# IO_wing.net
KiCad netlist of a schematic drawn in EAGLE
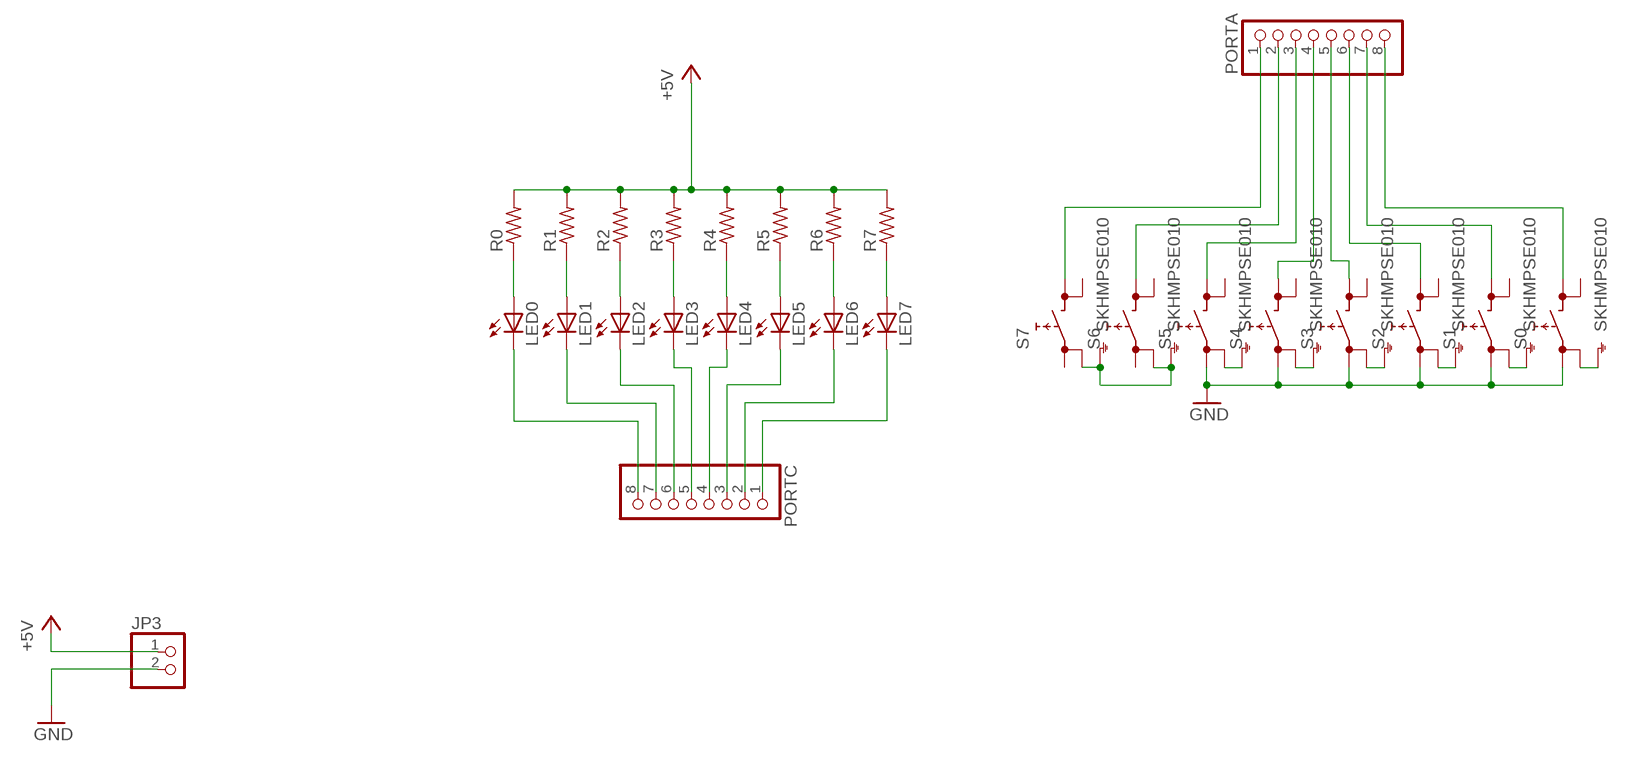
[diagram p0: schematic, sheet 1]

(export (version "E")
  (design (tool "Eeschema 10.0.6"))
  (components
    (comp (ref "JP3")
      (value "PINHD-1X2")
      (footprint "eagle-import:1X02")
      (libsource (lib "eagle-import") (part "PINHD-1X2"))
    )
    (comp (ref "LED0")
      (value "LEDCHIP-LED0805")
      (footprint "eagle-import:CHIP-LED0805")
      (libsource (lib "eagle-import") (part "LEDCHIP-LED0805"))
    )
    (comp (ref "LED1")
      (value "LEDCHIP-LED0805")
      (footprint "eagle-import:CHIP-LED0805")
      (libsource (lib "eagle-import") (part "LEDCHIP-LED0805"))
    )
    (comp (ref "LED2")
      (value "LEDCHIP-LED0805")
      (footprint "eagle-import:CHIP-LED0805")
      (libsource (lib "eagle-import") (part "LEDCHIP-LED0805"))
    )
    (comp (ref "LED3")
      (value "LEDCHIP-LED0805")
      (footprint "eagle-import:CHIP-LED0805")
      (libsource (lib "eagle-import") (part "LEDCHIP-LED0805"))
    )
    (comp (ref "LED4")
      (value "LEDCHIP-LED0805")
      (footprint "eagle-import:CHIP-LED0805")
      (libsource (lib "eagle-import") (part "LEDCHIP-LED0805"))
    )
    (comp (ref "LED5")
      (value "LEDCHIP-LED0805")
      (footprint "eagle-import:CHIP-LED0805")
      (libsource (lib "eagle-import") (part "LEDCHIP-LED0805"))
    )
    (comp (ref "LED6")
      (value "LEDCHIP-LED0805")
      (footprint "eagle-import:CHIP-LED0805")
      (libsource (lib "eagle-import") (part "LEDCHIP-LED0805"))
    )
    (comp (ref "LED7")
      (value "LEDCHIP-LED0805")
      (footprint "eagle-import:CHIP-LED0805")
      (libsource (lib "eagle-import") (part "LEDCHIP-LED0805"))
    )
    (comp (ref "PORTA")
      (value "PINHD-1X8")
      (footprint "eagle-import:1X08")
      (libsource (lib "eagle-import") (part "PINHD-1X8"))
    )
    (comp (ref "PORTC")
      (value "PINHD-1X8")
      (footprint "eagle-import:1X08")
      (libsource (lib "eagle-import") (part "PINHD-1X8"))
    )
    (comp (ref "R0")
      (value "R-US_R0805")
      (footprint "eagle-import:R0805")
      (libsource (lib "eagle-import") (part "R-US_R0805"))
    )
    (comp (ref "R1")
      (value "R-US_R0805")
      (footprint "eagle-import:R0805")
      (libsource (lib "eagle-import") (part "R-US_R0805"))
    )
    (comp (ref "R2")
      (value "R-US_R0805")
      (footprint "eagle-import:R0805")
      (libsource (lib "eagle-import") (part "R-US_R0805"))
    )
    (comp (ref "R3")
      (value "R-US_R0805")
      (footprint "eagle-import:R0805")
      (libsource (lib "eagle-import") (part "R-US_R0805"))
    )
    (comp (ref "R4")
      (value "R-US_R0805")
      (footprint "eagle-import:R0805")
      (libsource (lib "eagle-import") (part "R-US_R0805"))
    )
    (comp (ref "R5")
      (value "R-US_R0805")
      (footprint "eagle-import:R0805")
      (libsource (lib "eagle-import") (part "R-US_R0805"))
    )
    (comp (ref "R6")
      (value "R-US_R0805")
      (footprint "eagle-import:R0805")
      (libsource (lib "eagle-import") (part "R-US_R0805"))
    )
    (comp (ref "R7")
      (value "R-US_R0805")
      (footprint "eagle-import:R0805")
      (libsource (lib "eagle-import") (part "R-US_R0805"))
    )
    (comp (ref "S0")
      (value "SKHMPSE010")
      (footprint "eagle-import:SKHMPXE010")
      (libsource (lib "eagle-import") (part "SKHMPE010S"))
    )
    (comp (ref "S1")
      (value "SKHMPSE010")
      (footprint "eagle-import:SKHMPXE010")
      (libsource (lib "eagle-import") (part "SKHMPE010S"))
    )
    (comp (ref "S2")
      (value "SKHMPSE010")
      (footprint "eagle-import:SKHMPXE010")
      (libsource (lib "eagle-import") (part "SKHMPE010S"))
    )
    (comp (ref "S3")
      (value "SKHMPSE010")
      (footprint "eagle-import:SKHMPXE010")
      (libsource (lib "eagle-import") (part "SKHMPE010S"))
    )
    (comp (ref "S4")
      (value "SKHMPSE010")
      (footprint "eagle-import:SKHMPXE010")
      (libsource (lib "eagle-import") (part "SKHMPE010S"))
    )
    (comp (ref "S5")
      (value "SKHMPSE010")
      (footprint "eagle-import:SKHMPXE010")
      (libsource (lib "eagle-import") (part "SKHMPE010S"))
    )
    (comp (ref "S6")
      (value "SKHMPSE010")
      (footprint "eagle-import:SKHMPXE010")
      (libsource (lib "eagle-import") (part "SKHMPE010S"))
    )
    (comp (ref "S7")
      (value "SKHMPSE010")
      (footprint "eagle-import:SKHMPXE010")
      (libsource (lib "eagle-import") (part "SKHMPE010S"))
    )
  )
  (nets
    (net (code "1") (name "+5V") (class "Default")
      (node (ref "JP3") (pin "1") (pinfunction "1_1") (pintype "passive"))
      (node (ref "R0") (pin "2") (pinfunction "2_2") (pintype "passive"))
      (node (ref "R1") (pin "2") (pinfunction "2_2") (pintype "passive"))
      (node (ref "R2") (pin "2") (pinfunction "2_2") (pintype "passive"))
      (node (ref "R3") (pin "2") (pinfunction "2_2") (pintype "passive"))
      (node (ref "R4") (pin "2") (pinfunction "2_2") (pintype "passive"))
      (node (ref "R5") (pin "2") (pinfunction "2_2") (pintype "passive"))
      (node (ref "R6") (pin "2") (pinfunction "2_2") (pintype "passive"))
      (node (ref "R7") (pin "2") (pinfunction "2_2") (pintype "passive"))
    )
    (net (code "2") (name "GND") (class "Default")
      (node (ref "JP3") (pin "2") (pinfunction "2_2") (pintype "passive"))
      (node (ref "S0") (pin "1") (pinfunction "1.1_1") (pintype "passive"))
      (node (ref "S1") (pin "1") (pinfunction "1.1_1") (pintype "passive"))
      (node (ref "S2") (pin "1") (pinfunction "1.1_1") (pintype "passive"))
      (node (ref "S3") (pin "1") (pinfunction "1.1_1") (pintype "passive"))
      (node (ref "S4") (pin "1") (pinfunction "1.1_1") (pintype "passive"))
      (node (ref "S5") (pin "1") (pinfunction "1.1_1") (pintype "passive"))
    )
    (net (code "3") (name "Net-(LED0-PadA)") (class "Default")
      (node (ref "LED0") (pin "A") (pinfunction "A_A") (pintype "passive"))
      (node (ref "R0") (pin "1") (pinfunction "1_1") (pintype "passive"))
    )
    (net (code "4") (name "Net-(LED0-PadC)") (class "Default")
      (node (ref "LED0") (pin "C") (pinfunction "C_C") (pintype "passive"))
      (node (ref "PORTC") (pin "8") (pinfunction "8_8") (pintype "passive"))
    )
    (net (code "5") (name "Net-(LED1-PadA)") (class "Default")
      (node (ref "LED1") (pin "A") (pinfunction "A_A") (pintype "passive"))
      (node (ref "R1") (pin "1") (pinfunction "1_1") (pintype "passive"))
    )
    (net (code "6") (name "Net-(LED1-PadC)") (class "Default")
      (node (ref "LED1") (pin "C") (pinfunction "C_C") (pintype "passive"))
      (node (ref "PORTC") (pin "7") (pinfunction "7_7") (pintype "passive"))
    )
    (net (code "7") (name "Net-(LED2-PadA)") (class "Default")
      (node (ref "LED2") (pin "A") (pinfunction "A_A") (pintype "passive"))
      (node (ref "R2") (pin "1") (pinfunction "1_1") (pintype "passive"))
    )
    (net (code "8") (name "Net-(LED2-PadC)") (class "Default")
      (node (ref "LED2") (pin "C") (pinfunction "C_C") (pintype "passive"))
      (node (ref "PORTC") (pin "6") (pinfunction "6_6") (pintype "passive"))
    )
    (net (code "9") (name "Net-(LED3-PadA)") (class "Default")
      (node (ref "LED3") (pin "A") (pinfunction "A_A") (pintype "passive"))
      (node (ref "R3") (pin "1") (pinfunction "1_1") (pintype "passive"))
    )
    (net (code "10") (name "Net-(LED3-PadC)") (class "Default")
      (node (ref "LED3") (pin "C") (pinfunction "C_C") (pintype "passive"))
      (node (ref "PORTC") (pin "5") (pinfunction "5_5") (pintype "passive"))
    )
    (net (code "11") (name "Net-(LED4-PadA)") (class "Default")
      (node (ref "LED4") (pin "A") (pinfunction "A_A") (pintype "passive"))
      (node (ref "R4") (pin "1") (pinfunction "1_1") (pintype "passive"))
    )
    (net (code "12") (name "Net-(LED4-PadC)") (class "Default")
      (node (ref "LED4") (pin "C") (pinfunction "C_C") (pintype "passive"))
      (node (ref "PORTC") (pin "4") (pinfunction "4_4") (pintype "passive"))
    )
    (net (code "13") (name "Net-(LED5-PadA)") (class "Default")
      (node (ref "LED5") (pin "A") (pinfunction "A_A") (pintype "passive"))
      (node (ref "R5") (pin "1") (pinfunction "1_1") (pintype "passive"))
    )
    (net (code "14") (name "Net-(LED5-PadC)") (class "Default")
      (node (ref "LED5") (pin "C") (pinfunction "C_C") (pintype "passive"))
      (node (ref "PORTC") (pin "3") (pinfunction "3_3") (pintype "passive"))
    )
    (net (code "15") (name "Net-(LED6-PadA)") (class "Default")
      (node (ref "LED6") (pin "A") (pinfunction "A_A") (pintype "passive"))
      (node (ref "R6") (pin "1") (pinfunction "1_1") (pintype "passive"))
    )
    (net (code "16") (name "Net-(LED6-PadC)") (class "Default")
      (node (ref "LED6") (pin "C") (pinfunction "C_C") (pintype "passive"))
      (node (ref "PORTC") (pin "2") (pinfunction "2_2") (pintype "passive"))
    )
    (net (code "17") (name "Net-(LED7-PadA)") (class "Default")
      (node (ref "LED7") (pin "A") (pinfunction "A_A") (pintype "passive"))
      (node (ref "R7") (pin "1") (pinfunction "1_1") (pintype "passive"))
    )
    (net (code "18") (name "Net-(LED7-PadC)") (class "Default")
      (node (ref "LED7") (pin "C") (pinfunction "C_C") (pintype "passive"))
      (node (ref "PORTC") (pin "1") (pinfunction "1_1") (pintype "passive"))
    )
    (net (code "19") (name "Net-(S0-1.2)") (class "Default")
      (node (ref "S0") (pin "2") (pinfunction "1.2_2") (pintype "passive"))
      (node (ref "S0") (pin "5") (pinfunction "SH_5") (pintype "passive"))
    )
    (net (code "20") (name "Net-(S0-2.1)") (class "Default")
      (node (ref "PORTA") (pin "8") (pinfunction "8_8") (pintype "passive"))
      (node (ref "S0") (pin "3") (pinfunction "2.1_3") (pintype "passive"))
    )
    (net (code "21") (name "Net-(S1-1.2)") (class "Default")
      (node (ref "S1") (pin "2") (pinfunction "1.2_2") (pintype "passive"))
      (node (ref "S1") (pin "5") (pinfunction "SH_5") (pintype "passive"))
    )
    (net (code "22") (name "Net-(S1-2.1)") (class "Default")
      (node (ref "PORTA") (pin "7") (pinfunction "7_7") (pintype "passive"))
      (node (ref "S1") (pin "3") (pinfunction "2.1_3") (pintype "passive"))
    )
    (net (code "23") (name "Net-(S2-1.2)") (class "Default")
      (node (ref "S2") (pin "2") (pinfunction "1.2_2") (pintype "passive"))
      (node (ref "S2") (pin "5") (pinfunction "SH_5") (pintype "passive"))
    )
    (net (code "24") (name "Net-(S2-2.1)") (class "Default")
      (node (ref "PORTA") (pin "6") (pinfunction "6_6") (pintype "passive"))
      (node (ref "S2") (pin "3") (pinfunction "2.1_3") (pintype "passive"))
    )
    (net (code "25") (name "Net-(S3-1.2)") (class "Default")
      (node (ref "S3") (pin "2") (pinfunction "1.2_2") (pintype "passive"))
      (node (ref "S3") (pin "5") (pinfunction "SH_5") (pintype "passive"))
    )
    (net (code "26") (name "Net-(S3-2.1)") (class "Default")
      (node (ref "PORTA") (pin "5") (pinfunction "5_5") (pintype "passive"))
      (node (ref "S3") (pin "3") (pinfunction "2.1_3") (pintype "passive"))
    )
    (net (code "27") (name "Net-(S4-1.2)") (class "Default")
      (node (ref "S4") (pin "2") (pinfunction "1.2_2") (pintype "passive"))
      (node (ref "S4") (pin "5") (pinfunction "SH_5") (pintype "passive"))
    )
    (net (code "28") (name "Net-(S4-2.1)") (class "Default")
      (node (ref "PORTA") (pin "4") (pinfunction "4_4") (pintype "passive"))
      (node (ref "S4") (pin "3") (pinfunction "2.1_3") (pintype "passive"))
    )
    (net (code "29") (name "Net-(S5-1.2)") (class "Default")
      (node (ref "S5") (pin "2") (pinfunction "1.2_2") (pintype "passive"))
      (node (ref "S5") (pin "5") (pinfunction "SH_5") (pintype "passive"))
    )
    (net (code "30") (name "Net-(S5-2.1)") (class "Default")
      (node (ref "PORTA") (pin "3") (pinfunction "3_3") (pintype "passive"))
      (node (ref "S5") (pin "3") (pinfunction "2.1_3") (pintype "passive"))
    )
    (net (code "31") (name "Net-(S6-1.2)") (class "Default")
      (node (ref "S6") (pin "2") (pinfunction "1.2_2") (pintype "passive"))
      (node (ref "S6") (pin "5") (pinfunction "SH_5") (pintype "passive"))
      (node (ref "S7") (pin "2") (pinfunction "1.2_2") (pintype "passive"))
      (node (ref "S7") (pin "5") (pinfunction "SH_5") (pintype "passive"))
    )
    (net (code "32") (name "Net-(S6-2.1)") (class "Default")
      (node (ref "PORTA") (pin "2") (pinfunction "2_2") (pintype "passive"))
      (node (ref "S6") (pin "3") (pinfunction "2.1_3") (pintype "passive"))
    )
    (net (code "33") (name "Net-(S7-2.1)") (class "Default")
      (node (ref "PORTA") (pin "1") (pinfunction "1_1") (pintype "passive"))
      (node (ref "S7") (pin "3") (pinfunction "2.1_3") (pintype "passive"))
    )
    (net (code "34") (name "unconnected-(S0-2.2-Pad4)") (class "Default")
      (node (ref "S0") (pin "4") (pinfunction "2.2_4") (pintype "passive"))
    )
    (net (code "35") (name "unconnected-(S1-2.2-Pad4)") (class "Default")
      (node (ref "S1") (pin "4") (pinfunction "2.2_4") (pintype "passive"))
    )
    (net (code "36") (name "unconnected-(S2-2.2-Pad4)") (class "Default")
      (node (ref "S2") (pin "4") (pinfunction "2.2_4") (pintype "passive"))
    )
    (net (code "37") (name "unconnected-(S3-2.2-Pad4)") (class "Default")
      (node (ref "S3") (pin "4") (pinfunction "2.2_4") (pintype "passive"))
    )
    (net (code "38") (name "unconnected-(S4-2.2-Pad4)") (class "Default")
      (node (ref "S4") (pin "4") (pinfunction "2.2_4") (pintype "passive"))
    )
    (net (code "39") (name "unconnected-(S5-2.2-Pad4)") (class "Default")
      (node (ref "S5") (pin "4") (pinfunction "2.2_4") (pintype "passive"))
    )
    (net (code "40") (name "unconnected-(S6-1.1-Pad1)") (class "Default")
      (node (ref "S6") (pin "1") (pinfunction "1.1_1") (pintype "passive"))
    )
    (net (code "41") (name "unconnected-(S6-2.2-Pad4)") (class "Default")
      (node (ref "S6") (pin "4") (pinfunction "2.2_4") (pintype "passive"))
    )
    (net (code "42") (name "unconnected-(S7-1.1-Pad1)") (class "Default")
      (node (ref "S7") (pin "1") (pinfunction "1.1_1") (pintype "passive"))
    )
    (net (code "43") (name "unconnected-(S7-2.2-Pad4)") (class "Default")
      (node (ref "S7") (pin "4") (pinfunction "2.2_4") (pintype "passive"))
    )
  )
)
